# v1_0.net
KiCad netlist of a schematic drawn in EAGLE
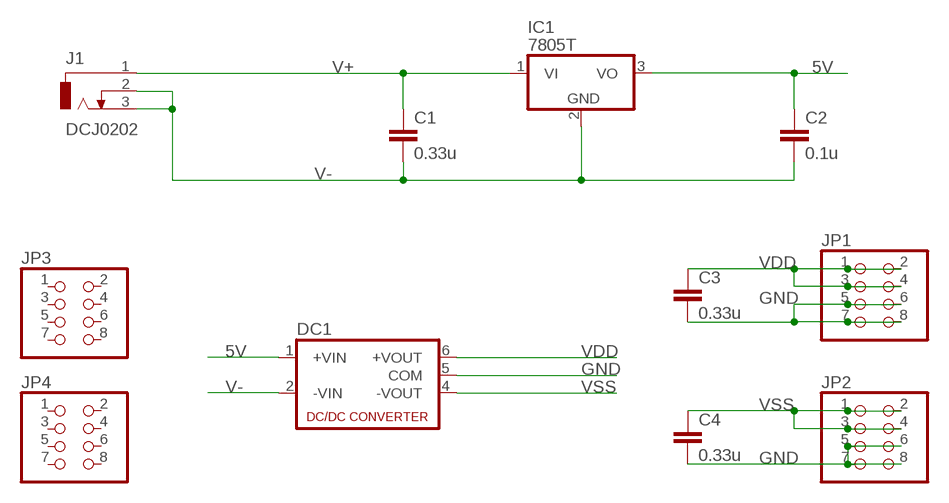
[diagram p0: schematic, sheet 1]

(export (version "E")
  (design (tool "Eeschema 10.0.6"))
  (components
    (comp (ref "C1")
      (value "0.33u")
      (footprint "eagle-import:C050-045X075")
      (libsource (lib "eagle-import") (part "C-EU050-045X075"))
    )
    (comp (ref "C2")
      (value "0.1u")
      (footprint "eagle-import:C050-045X075")
      (libsource (lib "eagle-import") (part "C-EU050-045X075"))
    )
    (comp (ref "C3")
      (value "0.33u")
      (footprint "eagle-import:C050-045X075")
      (libsource (lib "eagle-import") (part "C-EU050-045X075"))
    )
    (comp (ref "C4")
      (value "0.33u")
      (footprint "eagle-import:C050-045X075")
      (libsource (lib "eagle-import") (part "C-EU050-045X075"))
    )
    (comp (ref "DC1")
      (value "NMA")
      (footprint "eagle-import:NMA")
      (fields (field (name "MF") "C & D TECHNOLOGIES, INC") (field (name "MPN") "NMA0515SC"))
      (libsource (lib "eagle-import") (part "NMA"))
    )
    (comp (ref "IC1")
      (value "7805T")
      (footprint "eagle-import:TO220H")
      (libsource (lib "eagle-import") (part "78T05"))
    )
    (comp (ref "J1")
      (value "DCJ0202")
      (footprint "eagle-import:DCJ0202")
      (libsource (lib "eagle-import") (part "DCJ0202"))
    )
    (comp (ref "JP1")
      (value "PINHD-2X4")
      (footprint "eagle-import:2X04")
      (libsource (lib "eagle-import") (part "PINHD-2X4"))
    )
    (comp (ref "JP2")
      (value "PINHD-2X4")
      (footprint "eagle-import:2X04")
      (libsource (lib "eagle-import") (part "PINHD-2X4"))
    )
    (comp (ref "JP3")
      (value "PINHD-2X4")
      (footprint "eagle-import:2X04")
      (libsource (lib "eagle-import") (part "PINHD-2X4"))
    )
    (comp (ref "JP4")
      (value "PINHD-2X4")
      (footprint "eagle-import:2X04")
      (libsource (lib "eagle-import") (part "PINHD-2X4"))
    )
  )
  (nets
    (net (code "1") (name "/5V") (class "Default")
      (node (ref "C2") (pin "1") (pinfunction "1_1") (pintype "passive"))
      (node (ref "DC1") (pin "1") (pinfunction "+VIN_1") (pintype "passive"))
      (node (ref "IC1") (pin "3") (pinfunction "VO_3") (pintype "passive"))
    )
    (net (code "2") (name "/GND") (class "Default")
      (node (ref "C3") (pin "2") (pinfunction "2_2") (pintype "passive"))
      (node (ref "C4") (pin "2") (pinfunction "2_2") (pintype "passive"))
      (node (ref "DC1") (pin "5") (pinfunction "COM_5") (pintype "passive"))
      (node (ref "JP1") (pin "5") (pinfunction "5_5") (pintype "passive"))
      (node (ref "JP1") (pin "6") (pinfunction "6_6") (pintype "passive"))
      (node (ref "JP1") (pin "7") (pinfunction "7_7") (pintype "passive"))
      (node (ref "JP1") (pin "8") (pinfunction "8_8") (pintype "passive"))
      (node (ref "JP2") (pin "5") (pinfunction "5_5") (pintype "passive"))
      (node (ref "JP2") (pin "6") (pinfunction "6_6") (pintype "passive"))
      (node (ref "JP2") (pin "7") (pinfunction "7_7") (pintype "passive"))
      (node (ref "JP2") (pin "8") (pinfunction "8_8") (pintype "passive"))
    )
    (net (code "3") (name "/V+") (class "Default")
      (node (ref "C1") (pin "1") (pinfunction "1_1") (pintype "passive"))
      (node (ref "IC1") (pin "1") (pinfunction "VI_1") (pintype "input"))
      (node (ref "J1") (pin "1") (pinfunction "1_1") (pintype "passive"))
    )
    (net (code "4") (name "/V-") (class "Default")
      (node (ref "C1") (pin "2") (pinfunction "2_2") (pintype "passive"))
      (node (ref "C2") (pin "2") (pinfunction "2_2") (pintype "passive"))
      (node (ref "DC1") (pin "2") (pinfunction "-VIN_2") (pintype "passive"))
      (node (ref "IC1") (pin "2") (pinfunction "GND_2") (pintype "passive"))
      (node (ref "J1") (pin "2") (pinfunction "2_2") (pintype "passive"))
      (node (ref "J1") (pin "3") (pinfunction "3_3") (pintype "passive"))
    )
    (net (code "5") (name "/VDD") (class "Default")
      (node (ref "C3") (pin "1") (pinfunction "1_1") (pintype "passive"))
      (node (ref "DC1") (pin "6") (pinfunction "+VOUT_6") (pintype "passive"))
      (node (ref "JP1") (pin "1") (pinfunction "1_1") (pintype "passive"))
      (node (ref "JP1") (pin "2") (pinfunction "2_2") (pintype "passive"))
      (node (ref "JP1") (pin "3") (pinfunction "3_3") (pintype "passive"))
      (node (ref "JP1") (pin "4") (pinfunction "4_4") (pintype "passive"))
    )
    (net (code "6") (name "/VSS") (class "Default")
      (node (ref "C4") (pin "1") (pinfunction "1_1") (pintype "passive"))
      (node (ref "DC1") (pin "4") (pinfunction "-VOUT_4") (pintype "passive"))
      (node (ref "JP2") (pin "1") (pinfunction "1_1") (pintype "passive"))
      (node (ref "JP2") (pin "2") (pinfunction "2_2") (pintype "passive"))
      (node (ref "JP2") (pin "3") (pinfunction "3_3") (pintype "passive"))
      (node (ref "JP2") (pin "4") (pinfunction "4_4") (pintype "passive"))
    )
    (net (code "7") (name "unconnected-(JP3-Pad1)") (class "Default")
      (node (ref "JP3") (pin "1") (pinfunction "1_1") (pintype "passive"))
    )
    (net (code "8") (name "unconnected-(JP3-Pad2)") (class "Default")
      (node (ref "JP3") (pin "2") (pinfunction "2_2") (pintype "passive"))
    )
    (net (code "9") (name "unconnected-(JP3-Pad3)") (class "Default")
      (node (ref "JP3") (pin "3") (pinfunction "3_3") (pintype "passive"))
    )
    (net (code "10") (name "unconnected-(JP3-Pad4)") (class "Default")
      (node (ref "JP3") (pin "4") (pinfunction "4_4") (pintype "passive"))
    )
    (net (code "11") (name "unconnected-(JP3-Pad5)") (class "Default")
      (node (ref "JP3") (pin "5") (pinfunction "5_5") (pintype "passive"))
    )
    (net (code "12") (name "unconnected-(JP3-Pad6)") (class "Default")
      (node (ref "JP3") (pin "6") (pinfunction "6_6") (pintype "passive"))
    )
    (net (code "13") (name "unconnected-(JP3-Pad7)") (class "Default")
      (node (ref "JP3") (pin "7") (pinfunction "7_7") (pintype "passive"))
    )
    (net (code "14") (name "unconnected-(JP3-Pad8)") (class "Default")
      (node (ref "JP3") (pin "8") (pinfunction "8_8") (pintype "passive"))
    )
    (net (code "15") (name "unconnected-(JP4-Pad1)") (class "Default")
      (node (ref "JP4") (pin "1") (pinfunction "1_1") (pintype "passive"))
    )
    (net (code "16") (name "unconnected-(JP4-Pad2)") (class "Default")
      (node (ref "JP4") (pin "2") (pinfunction "2_2") (pintype "passive"))
    )
    (net (code "17") (name "unconnected-(JP4-Pad3)") (class "Default")
      (node (ref "JP4") (pin "3") (pinfunction "3_3") (pintype "passive"))
    )
    (net (code "18") (name "unconnected-(JP4-Pad4)") (class "Default")
      (node (ref "JP4") (pin "4") (pinfunction "4_4") (pintype "passive"))
    )
    (net (code "19") (name "unconnected-(JP4-Pad5)") (class "Default")
      (node (ref "JP4") (pin "5") (pinfunction "5_5") (pintype "passive"))
    )
    (net (code "20") (name "unconnected-(JP4-Pad6)") (class "Default")
      (node (ref "JP4") (pin "6") (pinfunction "6_6") (pintype "passive"))
    )
    (net (code "21") (name "unconnected-(JP4-Pad7)") (class "Default")
      (node (ref "JP4") (pin "7") (pinfunction "7_7") (pintype "passive"))
    )
    (net (code "22") (name "unconnected-(JP4-Pad8)") (class "Default")
      (node (ref "JP4") (pin "8") (pinfunction "8_8") (pintype "passive"))
    )
  )
)
